# USB_to_Serial.net
KiCad netlist of a schematic drawn in EAGLE
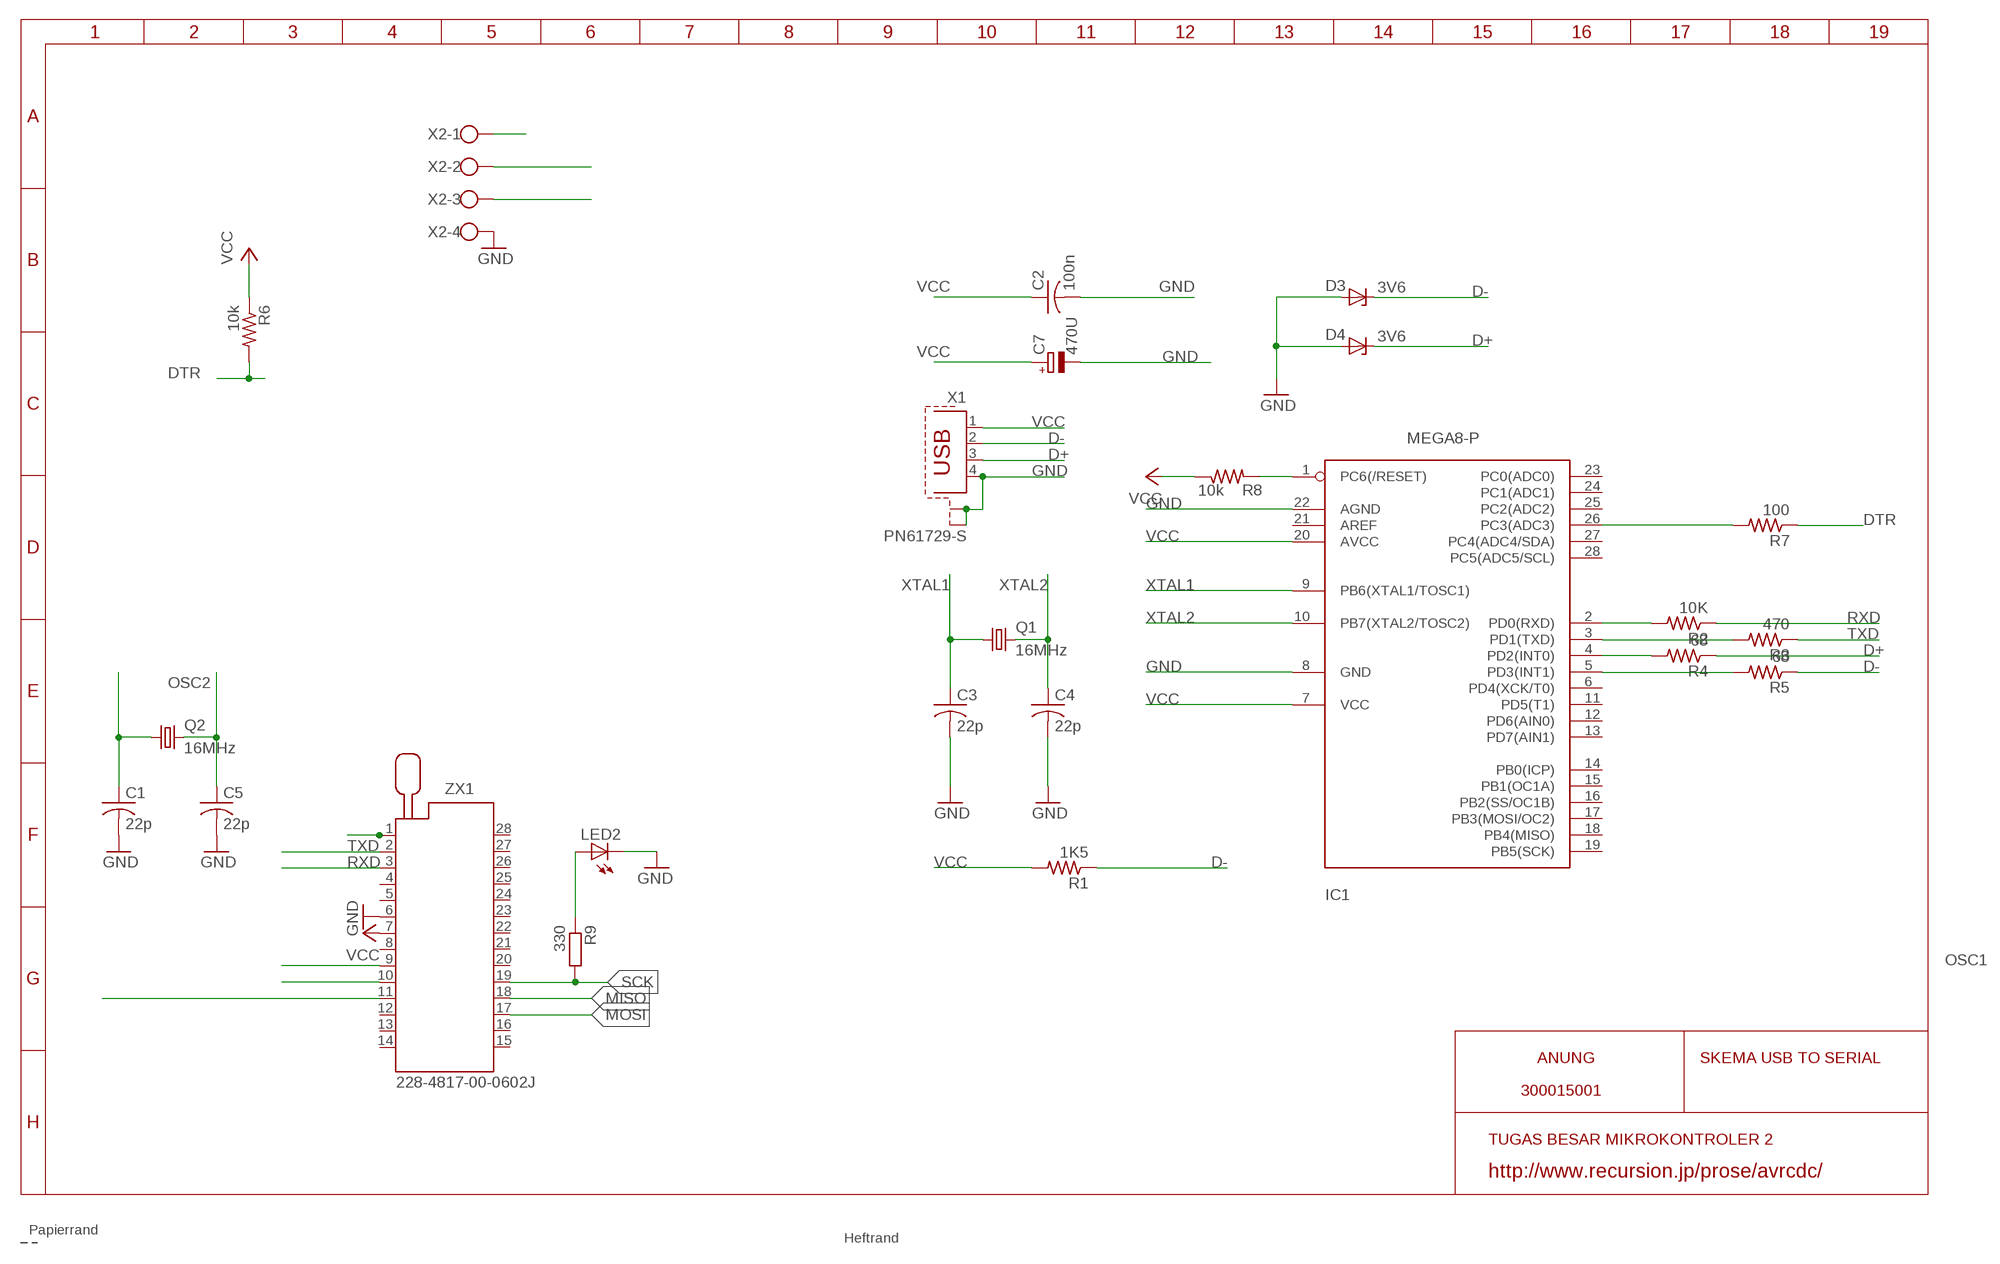
[diagram p0: schematic, sheet 1, part 1 of 2]
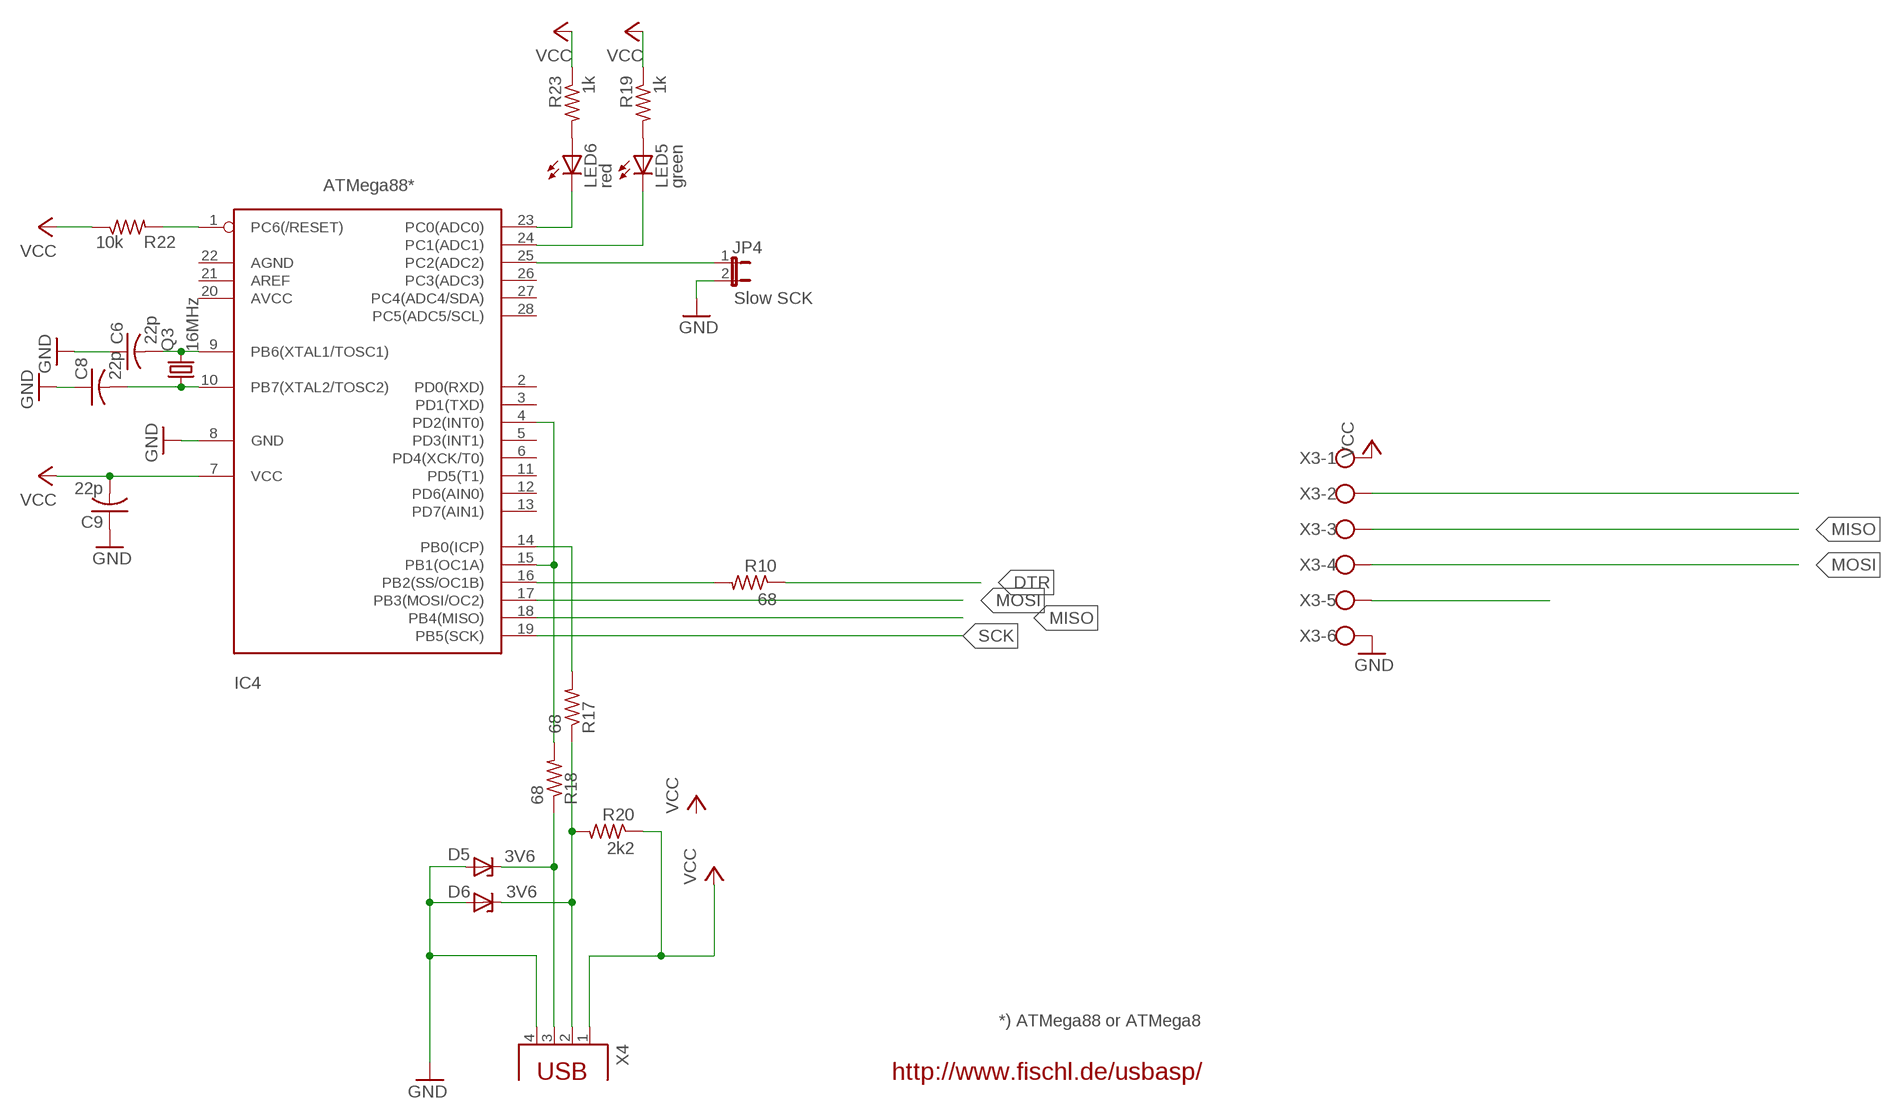
[diagram p1: schematic, sheet 1, part 2 of 2]

(export (version "E")
  (design (tool "Eeschema 10.0.6"))
  (components
    (comp (ref "C1")
      (value "22p")
      (footprint "eagle-import:C050-024X044")
      (libsource (lib "eagle-import") (part "C-US050-024X044"))
    )
    (comp (ref "C2")
      (value "100n")
      (footprint "eagle-import:C050-024X044")
      (libsource (lib "eagle-import") (part "C-US050-024X044"))
    )
    (comp (ref "C3")
      (value "22p")
      (footprint "eagle-import:C050-024X044")
      (libsource (lib "eagle-import") (part "C-US050-024X044"))
    )
    (comp (ref "C4")
      (value "22p")
      (footprint "eagle-import:C050-024X044")
      (libsource (lib "eagle-import") (part "C-US050-024X044"))
    )
    (comp (ref "C5")
      (value "22p")
      (footprint "eagle-import:C050-024X044")
      (libsource (lib "eagle-import") (part "C-US050-024X044"))
    )
    (comp (ref "C6")
      (value "22p")
      (footprint "eagle-import:C050-024X044")
      (libsource (lib "eagle-import") (part "C-US050-024X044"))
    )
    (comp (ref "C7")
      (value "470U")
      (footprint "eagle-import:E5-5")
      (libsource (lib "eagle-import") (part "CPOL-EUE5-5"))
    )
    (comp (ref "C8")
      (value "22p")
      (footprint "eagle-import:C050-024X044")
      (libsource (lib "eagle-import") (part "C-US050-024X044"))
    )
    (comp (ref "C9")
      (value "22p")
      (footprint "eagle-import:C050-024X044")
      (libsource (lib "eagle-import") (part "C-US050-024X044"))
    )
    (comp (ref "D3")
      (value "3V6")
      (footprint "eagle-import:DO34Z7")
      (libsource (lib "eagle-import") (part "ZENER-DIODEDO34-7"))
    )
    (comp (ref "D4")
      (value "3V6")
      (footprint "eagle-import:DO34Z7")
      (libsource (lib "eagle-import") (part "ZENER-DIODEDO34-7"))
    )
    (comp (ref "D5")
      (value "3V6")
      (footprint "eagle-import:DO34Z7")
      (libsource (lib "eagle-import") (part "ZENER-DIODEDO34-7"))
    )
    (comp (ref "D6")
      (value "3V6")
      (footprint "eagle-import:DO34Z7")
      (libsource (lib "eagle-import") (part "ZENER-DIODEDO34-7"))
    )
    (comp (ref "IC1")
      (value "MEGA8-P")
      (footprint "eagle-import:DIL28-3")
      (libsource (lib "eagle-import") (part "MEGA8-P"))
    )
    (comp (ref "IC4")
      (value "ATMega88*")
      (footprint "eagle-import:DIL28-3")
      (libsource (lib "eagle-import") (part "MEGA8-P"))
    )
    (comp (ref "JP4")
      (value "Slow SCK")
      (footprint "eagle-import:JP1")
      (libsource (lib "eagle-import") (part "JP1E"))
    )
    (comp (ref "LED2")
      (value "LED5MM")
      (footprint "eagle-import:LED5MM")
      (libsource (lib "eagle-import") (part "LED5MM"))
    )
    (comp (ref "LED5")
      (value "green")
      (footprint "eagle-import:LED5MM")
      (libsource (lib "eagle-import") (part "LED5MM"))
    )
    (comp (ref "LED6")
      (value "red")
      (footprint "eagle-import:LED5MM")
      (libsource (lib "eagle-import") (part "LED5MM"))
    )
    (comp (ref "Q1")
      (value "16MHz")
      (footprint "eagle-import:HC49_S")
      (libsource (lib "eagle-import") (part "CRYSTALHC49S"))
    )
    (comp (ref "Q2")
      (value "16MHz")
      (footprint "eagle-import:HC49_S")
      (libsource (lib "eagle-import") (part "CRYSTALHC49S"))
    )
    (comp (ref "Q3")
      (value "16MHz")
      (footprint "eagle-import:HC49_S")
      (libsource (lib "eagle-import") (part "CRYSTALHC49S"))
    )
    (comp (ref "R1")
      (value "1K5")
      (footprint "eagle-import:0207_7")
      (libsource (lib "eagle-import") (part "R-US_0207/7"))
    )
    (comp (ref "R2")
      (value "10K")
      (footprint "eagle-import:0207_7")
      (libsource (lib "eagle-import") (part "R-US_0207/7"))
    )
    (comp (ref "R3")
      (value "470")
      (footprint "eagle-import:0207_7")
      (libsource (lib "eagle-import") (part "R-US_0207/7"))
    )
    (comp (ref "R4")
      (value "68")
      (footprint "eagle-import:0207_7")
      (libsource (lib "eagle-import") (part "R-US_0207/7"))
    )
    (comp (ref "R5")
      (value "68")
      (footprint "eagle-import:0207_7")
      (libsource (lib "eagle-import") (part "R-US_0207/7"))
    )
    (comp (ref "R6")
      (value "10k")
      (footprint "eagle-import:0207_7")
      (libsource (lib "eagle-import") (part "R-US_0207/7"))
    )
    (comp (ref "R7")
      (value "100")
      (footprint "eagle-import:0207_7")
      (libsource (lib "eagle-import") (part "R-US_0207/7"))
    )
    (comp (ref "R8")
      (value "10k")
      (footprint "eagle-import:0207_10")
      (libsource (lib "eagle-import") (part "rcl_R-US_0207/10"))
    )
    (comp (ref "R9")
      (value "330")
      (footprint "eagle-import:0207_10")
      (libsource (lib "eagle-import") (part "R-EU_0207/10"))
    )
    (comp (ref "R10")
      (value "68")
      (footprint "eagle-import:0207_10")
      (libsource (lib "eagle-import") (part "rcl_R-US_0207/10"))
    )
    (comp (ref "R17")
      (value "68")
      (footprint "eagle-import:0207_10")
      (libsource (lib "eagle-import") (part "rcl_R-US_0207/10"))
    )
    (comp (ref "R18")
      (value "68")
      (footprint "eagle-import:0207_10")
      (libsource (lib "eagle-import") (part "rcl_R-US_0207/10"))
    )
    (comp (ref "R19")
      (value "1k")
      (footprint "eagle-import:0207_10")
      (libsource (lib "eagle-import") (part "rcl_R-US_0207/10"))
    )
    (comp (ref "R20")
      (value "2k2")
      (footprint "eagle-import:0207_10")
      (libsource (lib "eagle-import") (part "rcl_R-US_0207/10"))
    )
    (comp (ref "R22")
      (value "10k")
      (footprint "eagle-import:0207_10")
      (libsource (lib "eagle-import") (part "rcl_R-US_0207/10"))
    )
    (comp (ref "R23")
      (value "1k")
      (footprint "eagle-import:0207_10")
      (libsource (lib "eagle-import") (part "rcl_R-US_0207/10"))
    )
    (comp (ref "X1")
      (value "PN61729-S")
      (footprint "eagle-import:PN61729-S")
      (libsource (lib "eagle-import") (part "PN61729-S"))
    )
    (comp (ref "X2")
      (value "W237-4")
      (footprint "eagle-import:W237-4")
      (libsource (lib "eagle-import") (part "W237-4"))
    )
    (comp (ref "X3")
      (value "W237-6")
      (footprint "eagle-import:W237-6")
      (libsource (lib "eagle-import") (part "W237-6"))
    )
    (comp (ref "X4")
      (value "PN61729")
      (footprint "eagle-import:PN61729")
      (libsource (lib "eagle-import") (part "PN61729"))
    )
    (comp (ref "ZX1")
      (value "228-4817-00-0602J")
      (footprint "eagle-import:228-4817-00-0602J")
      (fields (field (name "MF") "3M"))
      (libsource (lib "eagle-import") (part "228-?00-0602J4817-"))
    )
  )
  (nets
    (net (code "1") (name "/D+") (class "Default")
      (node (ref "D4") (pin "C") (pinfunction "C_C") (pintype "passive"))
      (node (ref "R4") (pin "1") (pinfunction "1_1") (pintype "passive"))
      (node (ref "X1") (pin "3") (pinfunction "3_3") (pintype "passive"))
    )
    (net (code "2") (name "/D-") (class "Default")
      (node (ref "D3") (pin "C") (pinfunction "C_C") (pintype "passive"))
      (node (ref "R1") (pin "1") (pinfunction "1_1") (pintype "passive"))
      (node (ref "R5") (pin "1") (pinfunction "1_1") (pintype "passive"))
      (node (ref "X1") (pin "2") (pinfunction "2_2") (pintype "passive"))
    )
    (net (code "3") (name "/N$1") (class "Default")
      (node (ref "IC4") (pin "16") (pinfunction "PB2(SS/OC1B)_16") (pintype "bidirectional"))
      (node (ref "R10") (pin "2") (pinfunction "2_2") (pintype "passive"))
      (node (ref "X3") (pin "5") (pinfunction "KL_5") (pintype "passive"))
    )
    (net (code "4") (name "/OSC1") (class "Default")
      (node (ref "C1") (pin "1") (pinfunction "1_1") (pintype "passive"))
      (node (ref "Q2") (pin "1") (pinfunction "1_1") (pintype "passive"))
      (node (ref "ZX1") (pin "9") (pinfunction "9_9") (pintype "passive"))
    )
    (net (code "5") (name "/OSC2") (class "Default")
      (node (ref "C5") (pin "1") (pinfunction "1_1") (pintype "passive"))
      (node (ref "Q2") (pin "2") (pinfunction "2_2") (pintype "passive"))
      (node (ref "ZX1") (pin "10") (pinfunction "10_10") (pintype "passive"))
    )
    (net (code "6") (name "/RXD") (class "Default")
      (node (ref "R2") (pin "1") (pinfunction "1_1") (pintype "passive"))
      (node (ref "X2") (pin "3") (pinfunction "KL_3") (pintype "passive"))
      (node (ref "ZX1") (pin "3") (pinfunction "3_3") (pintype "passive"))
    )
    (net (code "7") (name "/TXD") (class "Default")
      (node (ref "R3") (pin "1") (pinfunction "1_1") (pintype "passive"))
      (node (ref "X2") (pin "2") (pinfunction "KL_2") (pintype "passive"))
      (node (ref "ZX1") (pin "2") (pinfunction "2_2") (pintype "passive"))
    )
    (net (code "8") (name "/XTAL1") (class "Default")
      (node (ref "C3") (pin "1") (pinfunction "1_1") (pintype "passive"))
      (node (ref "IC1") (pin "9") (pinfunction "PB6(XTAL1/TOSC1)_9") (pintype "bidirectional"))
      (node (ref "Q1") (pin "1") (pinfunction "1_1") (pintype "passive"))
    )
    (net (code "9") (name "/XTAL2") (class "Default")
      (node (ref "C4") (pin "1") (pinfunction "1_1") (pintype "passive"))
      (node (ref "IC1") (pin "10") (pinfunction "PB7(XTAL2/TOSC2)_10") (pintype "bidirectional"))
      (node (ref "Q1") (pin "2") (pinfunction "2_2") (pintype "passive"))
    )
    (net (code "10") (name "DTR") (class "Default")
      (node (ref "R10") (pin "1") (pinfunction "1_1") (pintype "passive"))
      (node (ref "R6") (pin "2") (pinfunction "2_2") (pintype "passive"))
      (node (ref "R7") (pin "1") (pinfunction "1_1") (pintype "passive"))
      (node (ref "X2") (pin "1") (pinfunction "KL_1") (pintype "passive"))
      (node (ref "ZX1") (pin "1") (pinfunction "1_1") (pintype "passive"))
    )
    (net (code "11") (name "GND") (class "Default")
      (node (ref "C1") (pin "2") (pinfunction "2_2") (pintype "passive"))
      (node (ref "C2") (pin "2") (pinfunction "2_2") (pintype "passive"))
      (node (ref "C3") (pin "2") (pinfunction "2_2") (pintype "passive"))
      (node (ref "C4") (pin "2") (pinfunction "2_2") (pintype "passive"))
      (node (ref "C5") (pin "2") (pinfunction "2_2") (pintype "passive"))
      (node (ref "C6") (pin "1") (pinfunction "1_1") (pintype "passive"))
      (node (ref "C7") (pin "-") (pinfunction "-_-") (pintype "passive"))
      (node (ref "C8") (pin "1") (pinfunction "1_1") (pintype "passive"))
      (node (ref "C9") (pin "1") (pinfunction "1_1") (pintype "passive"))
      (node (ref "D3") (pin "A") (pinfunction "A_A") (pintype "passive"))
      (node (ref "D4") (pin "A") (pinfunction "A_A") (pintype "passive"))
      (node (ref "D5") (pin "A") (pinfunction "A_A") (pintype "passive"))
      (node (ref "D6") (pin "A") (pinfunction "A_A") (pintype "passive"))
      (node (ref "IC1") (pin "22") (pinfunction "AGND_22") (pintype "bidirectional"))
      (node (ref "IC1") (pin "8") (pinfunction "GND_8") (pintype "bidirectional"))
      (node (ref "IC4") (pin "8") (pinfunction "GND_8") (pintype "bidirectional"))
      (node (ref "JP4") (pin "2") (pinfunction "2_2") (pintype "passive"))
      (node (ref "LED2") (pin "K") (pinfunction "C_K") (pintype "passive"))
      (node (ref "X1") (pin "4") (pinfunction "4_4") (pintype "passive"))
      (node (ref "X1") (pin "S1") (pinfunction "S1_S1") (pintype "passive"))
      (node (ref "X1") (pin "S2") (pinfunction "S2_S2") (pintype "passive"))
      (node (ref "X2") (pin "4") (pinfunction "KL_4") (pintype "passive"))
      (node (ref "X3") (pin "6") (pinfunction "KL_6") (pintype "passive"))
      (node (ref "X4") (pin "4") (pinfunction "4_4") (pintype "bidirectional"))
      (node (ref "ZX1") (pin "6") (pinfunction "6_6") (pintype "passive"))
    )
    (net (code "12") (name "MISO") (class "Default")
      (node (ref "IC4") (pin "18") (pinfunction "PB4(MISO)_18") (pintype "bidirectional"))
      (node (ref "X3") (pin "3") (pinfunction "KL_3") (pintype "passive"))
      (node (ref "ZX1") (pin "18") (pinfunction "18_18") (pintype "passive"))
    )
    (net (code "13") (name "MOSI") (class "Default")
      (node (ref "IC4") (pin "17") (pinfunction "PB3(MOSI/OC2)_17") (pintype "bidirectional"))
      (node (ref "X3") (pin "4") (pinfunction "KL_4") (pintype "passive"))
      (node (ref "ZX1") (pin "17") (pinfunction "17_17") (pintype "passive"))
    )
    (net (code "14") (name "Net-(D5-PadC)") (class "Default")
      (node (ref "D5") (pin "C") (pinfunction "C_C") (pintype "passive"))
      (node (ref "R18") (pin "1") (pinfunction "1_1") (pintype "passive"))
      (node (ref "X4") (pin "3") (pinfunction "3_3") (pintype "bidirectional"))
    )
    (net (code "15") (name "Net-(D6-PadC)") (class "Default")
      (node (ref "D6") (pin "C") (pinfunction "C_C") (pintype "passive"))
      (node (ref "R17") (pin "1") (pinfunction "1_1") (pintype "passive"))
      (node (ref "R20") (pin "2") (pinfunction "2_2") (pintype "passive"))
      (node (ref "X4") (pin "2") (pinfunction "2_2") (pintype "bidirectional"))
    )
    (net (code "16") (name "Net-(IC1-PC3(ADC3))") (class "Default")
      (node (ref "IC1") (pin "26") (pinfunction "PC3(ADC3)_26") (pintype "bidirectional"))
      (node (ref "R7") (pin "2") (pinfunction "2_2") (pintype "passive"))
    )
    (net (code "17") (name "Net-(IC1-PC6({slash}RESET))") (class "Default")
      (node (ref "IC1") (pin "1") (pinfunction "PC6(/RESET)_1") (pintype "bidirectional"))
      (node (ref "R8") (pin "2") (pinfunction "2_2") (pintype "passive"))
    )
    (net (code "18") (name "Net-(IC1-PD0(RXD))") (class "Default")
      (node (ref "IC1") (pin "2") (pinfunction "PD0(RXD)_2") (pintype "bidirectional"))
      (node (ref "R2") (pin "2") (pinfunction "2_2") (pintype "passive"))
    )
    (net (code "19") (name "Net-(IC1-PD1(TXD))") (class "Default")
      (node (ref "IC1") (pin "3") (pinfunction "PD1(TXD)_3") (pintype "bidirectional"))
      (node (ref "R3") (pin "2") (pinfunction "2_2") (pintype "passive"))
    )
    (net (code "20") (name "Net-(IC1-PD2(INT0))") (class "Default")
      (node (ref "IC1") (pin "4") (pinfunction "PD2(INT0)_4") (pintype "bidirectional"))
      (node (ref "R4") (pin "2") (pinfunction "2_2") (pintype "passive"))
    )
    (net (code "21") (name "Net-(IC1-PD3(INT1))") (class "Default")
      (node (ref "IC1") (pin "5") (pinfunction "PD3(INT1)_5") (pintype "bidirectional"))
      (node (ref "R5") (pin "2") (pinfunction "2_2") (pintype "passive"))
    )
    (net (code "22") (name "Net-(IC4-PB0(ICP))") (class "Default")
      (node (ref "IC4") (pin "14") (pinfunction "PB0(ICP)_14") (pintype "bidirectional"))
      (node (ref "R17") (pin "2") (pinfunction "2_2") (pintype "passive"))
    )
    (net (code "23") (name "Net-(IC4-PB1(OC1A))") (class "Default")
      (node (ref "IC4") (pin "15") (pinfunction "PB1(OC1A)_15") (pintype "bidirectional"))
      (node (ref "IC4") (pin "4") (pinfunction "PD2(INT0)_4") (pintype "bidirectional"))
      (node (ref "R18") (pin "2") (pinfunction "2_2") (pintype "passive"))
    )
    (net (code "24") (name "Net-(IC4-PB6(XTAL1{slash}TOSC1))") (class "Default")
      (node (ref "C6") (pin "2") (pinfunction "2_2") (pintype "passive"))
      (node (ref "IC4") (pin "9") (pinfunction "PB6(XTAL1/TOSC1)_9") (pintype "bidirectional"))
      (node (ref "Q3") (pin "2") (pinfunction "2_2") (pintype "passive"))
    )
    (net (code "25") (name "Net-(IC4-PB7(XTAL2{slash}TOSC2))") (class "Default")
      (node (ref "C8") (pin "2") (pinfunction "2_2") (pintype "passive"))
      (node (ref "IC4") (pin "10") (pinfunction "PB7(XTAL2/TOSC2)_10") (pintype "bidirectional"))
      (node (ref "Q3") (pin "1") (pinfunction "1_1") (pintype "passive"))
    )
    (net (code "26") (name "Net-(IC4-PC0(ADC0))") (class "Default")
      (node (ref "IC4") (pin "23") (pinfunction "PC0(ADC0)_23") (pintype "bidirectional"))
      (node (ref "LED6") (pin "K") (pinfunction "C_K") (pintype "passive"))
    )
    (net (code "27") (name "Net-(IC4-PC1(ADC1))") (class "Default")
      (node (ref "IC4") (pin "24") (pinfunction "PC1(ADC1)_24") (pintype "bidirectional"))
      (node (ref "LED5") (pin "K") (pinfunction "C_K") (pintype "passive"))
    )
    (net (code "28") (name "Net-(IC4-PC2(ADC2))") (class "Default")
      (node (ref "IC4") (pin "25") (pinfunction "PC2(ADC2)_25") (pintype "bidirectional"))
      (node (ref "JP4") (pin "1") (pinfunction "1_1") (pintype "passive"))
    )
    (net (code "29") (name "Net-(IC4-PC6({slash}RESET))") (class "Default")
      (node (ref "IC4") (pin "1") (pinfunction "PC6(/RESET)_1") (pintype "bidirectional"))
      (node (ref "R22") (pin "2") (pinfunction "2_2") (pintype "passive"))
    )
    (net (code "30") (name "Net-(LED2-PadA)") (class "Default")
      (node (ref "LED2") (pin "A") (pinfunction "A_A") (pintype "passive"))
      (node (ref "R9") (pin "1") (pinfunction "1_1") (pintype "passive"))
    )
    (net (code "31") (name "Net-(LED5-PadA)") (class "Default")
      (node (ref "LED5") (pin "A") (pinfunction "A_A") (pintype "passive"))
      (node (ref "R19") (pin "2") (pinfunction "2_2") (pintype "passive"))
    )
    (net (code "32") (name "Net-(LED6-PadA)") (class "Default")
      (node (ref "LED6") (pin "A") (pinfunction "A_A") (pintype "passive"))
      (node (ref "R23") (pin "2") (pinfunction "2_2") (pintype "passive"))
    )
    (net (code "33") (name "SCK") (class "Default")
      (node (ref "IC4") (pin "19") (pinfunction "PB5(SCK)_19") (pintype "bidirectional"))
      (node (ref "R9") (pin "2") (pinfunction "2_2") (pintype "passive"))
      (node (ref "X3") (pin "2") (pinfunction "KL_2") (pintype "passive"))
      (node (ref "ZX1") (pin "19") (pinfunction "19_19") (pintype "passive"))
    )
    (net (code "34") (name "VCC") (class "Default")
      (node (ref "C2") (pin "1") (pinfunction "1_1") (pintype "passive"))
      (node (ref "C7") (pin "+") (pinfunction "+_+") (pintype "passive"))
      (node (ref "C9") (pin "2") (pinfunction "2_2") (pintype "passive"))
      (node (ref "IC1") (pin "20") (pinfunction "AVCC_20") (pintype "bidirectional"))
      (node (ref "IC1") (pin "7") (pinfunction "VCC_7") (pintype "bidirectional"))
      (node (ref "IC4") (pin "7") (pinfunction "VCC_7") (pintype "bidirectional"))
      (node (ref "R1") (pin "2") (pinfunction "2_2") (pintype "passive"))
      (node (ref "R19") (pin "1") (pinfunction "1_1") (pintype "passive"))
      (node (ref "R20") (pin "1") (pinfunction "1_1") (pintype "passive"))
      (node (ref "R22") (pin "1") (pinfunction "1_1") (pintype "passive"))
      (node (ref "R23") (pin "1") (pinfunction "1_1") (pintype "passive"))
      (node (ref "R6") (pin "1") (pinfunction "1_1") (pintype "passive"))
      (node (ref "R8") (pin "1") (pinfunction "1_1") (pintype "passive"))
      (node (ref "X1") (pin "1") (pinfunction "1_1") (pintype "passive"))
      (node (ref "X3") (pin "1") (pinfunction "KL_1") (pintype "passive"))
      (node (ref "X4") (pin "1") (pinfunction "1_1") (pintype "bidirectional"))
      (node (ref "ZX1") (pin "7") (pinfunction "7_7") (pintype "passive"))
    )
    (net (code "35") (name "unconnected-(IC1-AREF-Pad21)") (class "Default")
      (node (ref "IC1") (pin "21") (pinfunction "AREF_21") (pintype "bidirectional"))
    )
    (net (code "36") (name "unconnected-(IC1-PB0(ICP)-Pad14)") (class "Default")
      (node (ref "IC1") (pin "14") (pinfunction "PB0(ICP)_14") (pintype "bidirectional"))
    )
    (net (code "37") (name "unconnected-(IC1-PB1(OC1A)-Pad15)") (class "Default")
      (node (ref "IC1") (pin "15") (pinfunction "PB1(OC1A)_15") (pintype "bidirectional"))
    )
    (net (code "38") (name "unconnected-(IC1-PB2(SS{slash}OC1B)-Pad16)") (class "Default")
      (node (ref "IC1") (pin "16") (pinfunction "PB2(SS/OC1B)_16") (pintype "bidirectional"))
    )
    (net (code "39") (name "unconnected-(IC1-PB3(MOSI{slash}OC2)-Pad17)") (class "Default")
      (node (ref "IC1") (pin "17") (pinfunction "PB3(MOSI/OC2)_17") (pintype "bidirectional"))
    )
    (net (code "40") (name "unconnected-(IC1-PB4(MISO)-Pad18)") (class "Default")
      (node (ref "IC1") (pin "18") (pinfunction "PB4(MISO)_18") (pintype "bidirectional"))
    )
    (net (code "41") (name "unconnected-(IC1-PB5(SCK)-Pad19)") (class "Default")
      (node (ref "IC1") (pin "19") (pinfunction "PB5(SCK)_19") (pintype "bidirectional"))
    )
    (net (code "42") (name "unconnected-(IC1-PC0(ADC0)-Pad23)") (class "Default")
      (node (ref "IC1") (pin "23") (pinfunction "PC0(ADC0)_23") (pintype "bidirectional"))
    )
    (net (code "43") (name "unconnected-(IC1-PC1(ADC1)-Pad24)") (class "Default")
      (node (ref "IC1") (pin "24") (pinfunction "PC1(ADC1)_24") (pintype "bidirectional"))
    )
    (net (code "44") (name "unconnected-(IC1-PC2(ADC2)-Pad25)") (class "Default")
      (node (ref "IC1") (pin "25") (pinfunction "PC2(ADC2)_25") (pintype "bidirectional"))
    )
    (net (code "45") (name "unconnected-(IC1-PC4(ADC4{slash}SDA)-Pad27)") (class "Default")
      (node (ref "IC1") (pin "27") (pinfunction "PC4(ADC4/SDA)_27") (pintype "bidirectional"))
    )
    (net (code "46") (name "unconnected-(IC1-PC5(ADC5{slash}SCL)-Pad28)") (class "Default")
      (node (ref "IC1") (pin "28") (pinfunction "PC5(ADC5/SCL)_28") (pintype "bidirectional"))
    )
    (net (code "47") (name "unconnected-(IC1-PD4(XCK{slash}T0)-Pad6)") (class "Default")
      (node (ref "IC1") (pin "6") (pinfunction "PD4(XCK/T0)_6") (pintype "bidirectional"))
    )
    (net (code "48") (name "unconnected-(IC1-PD5(T1)-Pad11)") (class "Default")
      (node (ref "IC1") (pin "11") (pinfunction "PD5(T1)_11") (pintype "bidirectional"))
    )
    (net (code "49") (name "unconnected-(IC1-PD6(AIN0)-Pad12)") (class "Default")
      (node (ref "IC1") (pin "12") (pinfunction "PD6(AIN0)_12") (pintype "bidirectional"))
    )
    (net (code "50") (name "unconnected-(IC1-PD7(AIN1)-Pad13)") (class "Default")
      (node (ref "IC1") (pin "13") (pinfunction "PD7(AIN1)_13") (pintype "bidirectional"))
    )
    (net (code "51") (name "unconnected-(IC4-AGND-Pad22)") (class "Default")
      (node (ref "IC4") (pin "22") (pinfunction "AGND_22") (pintype "bidirectional"))
    )
    (net (code "52") (name "unconnected-(IC4-AREF-Pad21)") (class "Default")
      (node (ref "IC4") (pin "21") (pinfunction "AREF_21") (pintype "bidirectional"))
    )
    (net (code "53") (name "unconnected-(IC4-AVCC-Pad20)") (class "Default")
      (node (ref "IC4") (pin "20") (pinfunction "AVCC_20") (pintype "bidirectional"))
    )
    (net (code "54") (name "unconnected-(IC4-PC3(ADC3)-Pad26)") (class "Default")
      (node (ref "IC4") (pin "26") (pinfunction "PC3(ADC3)_26") (pintype "bidirectional"))
    )
    (net (code "55") (name "unconnected-(IC4-PC4(ADC4{slash}SDA)-Pad27)") (class "Default")
      (node (ref "IC4") (pin "27") (pinfunction "PC4(ADC4/SDA)_27") (pintype "bidirectional"))
    )
    (net (code "56") (name "unconnected-(IC4-PC5(ADC5{slash}SCL)-Pad28)") (class "Default")
      (node (ref "IC4") (pin "28") (pinfunction "PC5(ADC5/SCL)_28") (pintype "bidirectional"))
    )
    (net (code "57") (name "unconnected-(IC4-PD0(RXD)-Pad2)") (class "Default")
      (node (ref "IC4") (pin "2") (pinfunction "PD0(RXD)_2") (pintype "bidirectional"))
    )
    (net (code "58") (name "unconnected-(IC4-PD1(TXD)-Pad3)") (class "Default")
      (node (ref "IC4") (pin "3") (pinfunction "PD1(TXD)_3") (pintype "bidirectional"))
    )
    (net (code "59") (name "unconnected-(IC4-PD3(INT1)-Pad5)") (class "Default")
      (node (ref "IC4") (pin "5") (pinfunction "PD3(INT1)_5") (pintype "bidirectional"))
    )
    (net (code "60") (name "unconnected-(IC4-PD4(XCK{slash}T0)-Pad6)") (class "Default")
      (node (ref "IC4") (pin "6") (pinfunction "PD4(XCK/T0)_6") (pintype "bidirectional"))
    )
    (net (code "61") (name "unconnected-(IC4-PD5(T1)-Pad11)") (class "Default")
      (node (ref "IC4") (pin "11") (pinfunction "PD5(T1)_11") (pintype "bidirectional"))
    )
    (net (code "62") (name "unconnected-(IC4-PD6(AIN0)-Pad12)") (class "Default")
      (node (ref "IC4") (pin "12") (pinfunction "PD6(AIN0)_12") (pintype "bidirectional"))
    )
    (net (code "63") (name "unconnected-(IC4-PD7(AIN1)-Pad13)") (class "Default")
      (node (ref "IC4") (pin "13") (pinfunction "PD7(AIN1)_13") (pintype "bidirectional"))
    )
    (net (code "64") (name "unconnected-(ZX1-Pad4)") (class "Default")
      (node (ref "ZX1") (pin "4") (pinfunction "4_4") (pintype "passive"))
    )
    (net (code "65") (name "unconnected-(ZX1-Pad5)") (class "Default")
      (node (ref "ZX1") (pin "5") (pinfunction "5_5") (pintype "passive"))
    )
    (net (code "66") (name "unconnected-(ZX1-Pad8)") (class "Default")
      (node (ref "ZX1") (pin "8") (pinfunction "8_8") (pintype "passive"))
    )
    (net (code "67") (name "unconnected-(ZX1-Pad11)") (class "Default")
      (node (ref "ZX1") (pin "11") (pinfunction "11_11") (pintype "passive"))
    )
    (net (code "68") (name "unconnected-(ZX1-Pad12)") (class "Default")
      (node (ref "ZX1") (pin "12") (pinfunction "12_12") (pintype "passive"))
    )
    (net (code "69") (name "unconnected-(ZX1-Pad13)") (class "Default")
      (node (ref "ZX1") (pin "13") (pinfunction "13_13") (pintype "passive"))
    )
    (net (code "70") (name "unconnected-(ZX1-Pad14)") (class "Default")
      (node (ref "ZX1") (pin "14") (pinfunction "14_14") (pintype "passive"))
    )
    (net (code "71") (name "unconnected-(ZX1-Pad15)") (class "Default")
      (node (ref "ZX1") (pin "15") (pinfunction "15_15") (pintype "passive"))
    )
    (net (code "72") (name "unconnected-(ZX1-Pad16)") (class "Default")
      (node (ref "ZX1") (pin "16") (pinfunction "16_16") (pintype "passive"))
    )
    (net (code "73") (name "unconnected-(ZX1-Pad20)") (class "Default")
      (node (ref "ZX1") (pin "20") (pinfunction "20_20") (pintype "passive"))
    )
    (net (code "74") (name "unconnected-(ZX1-Pad21)") (class "Default")
      (node (ref "ZX1") (pin "21") (pinfunction "21_21") (pintype "passive"))
    )
    (net (code "75") (name "unconnected-(ZX1-Pad22)") (class "Default")
      (node (ref "ZX1") (pin "22") (pinfunction "22_22") (pintype "passive"))
    )
    (net (code "76") (name "unconnected-(ZX1-Pad23)") (class "Default")
      (node (ref "ZX1") (pin "23") (pinfunction "23_23") (pintype "passive"))
    )
    (net (code "77") (name "unconnected-(ZX1-Pad24)") (class "Default")
      (node (ref "ZX1") (pin "24") (pinfunction "24_24") (pintype "passive"))
    )
    (net (code "78") (name "unconnected-(ZX1-Pad25)") (class "Default")
      (node (ref "ZX1") (pin "25") (pinfunction "25_25") (pintype "passive"))
    )
    (net (code "79") (name "unconnected-(ZX1-Pad26)") (class "Default")
      (node (ref "ZX1") (pin "26") (pinfunction "26_26") (pintype "passive"))
    )
    (net (code "80") (name "unconnected-(ZX1-Pad27)") (class "Default")
      (node (ref "ZX1") (pin "27") (pinfunction "27_27") (pintype "passive"))
    )
    (net (code "81") (name "unconnected-(ZX1-Pad28)") (class "Default")
      (node (ref "ZX1") (pin "28") (pinfunction "28_28") (pintype "passive"))
    )
  )
)
